# 1.net
KiCad netlist of a schematic drawn in Altium Designer
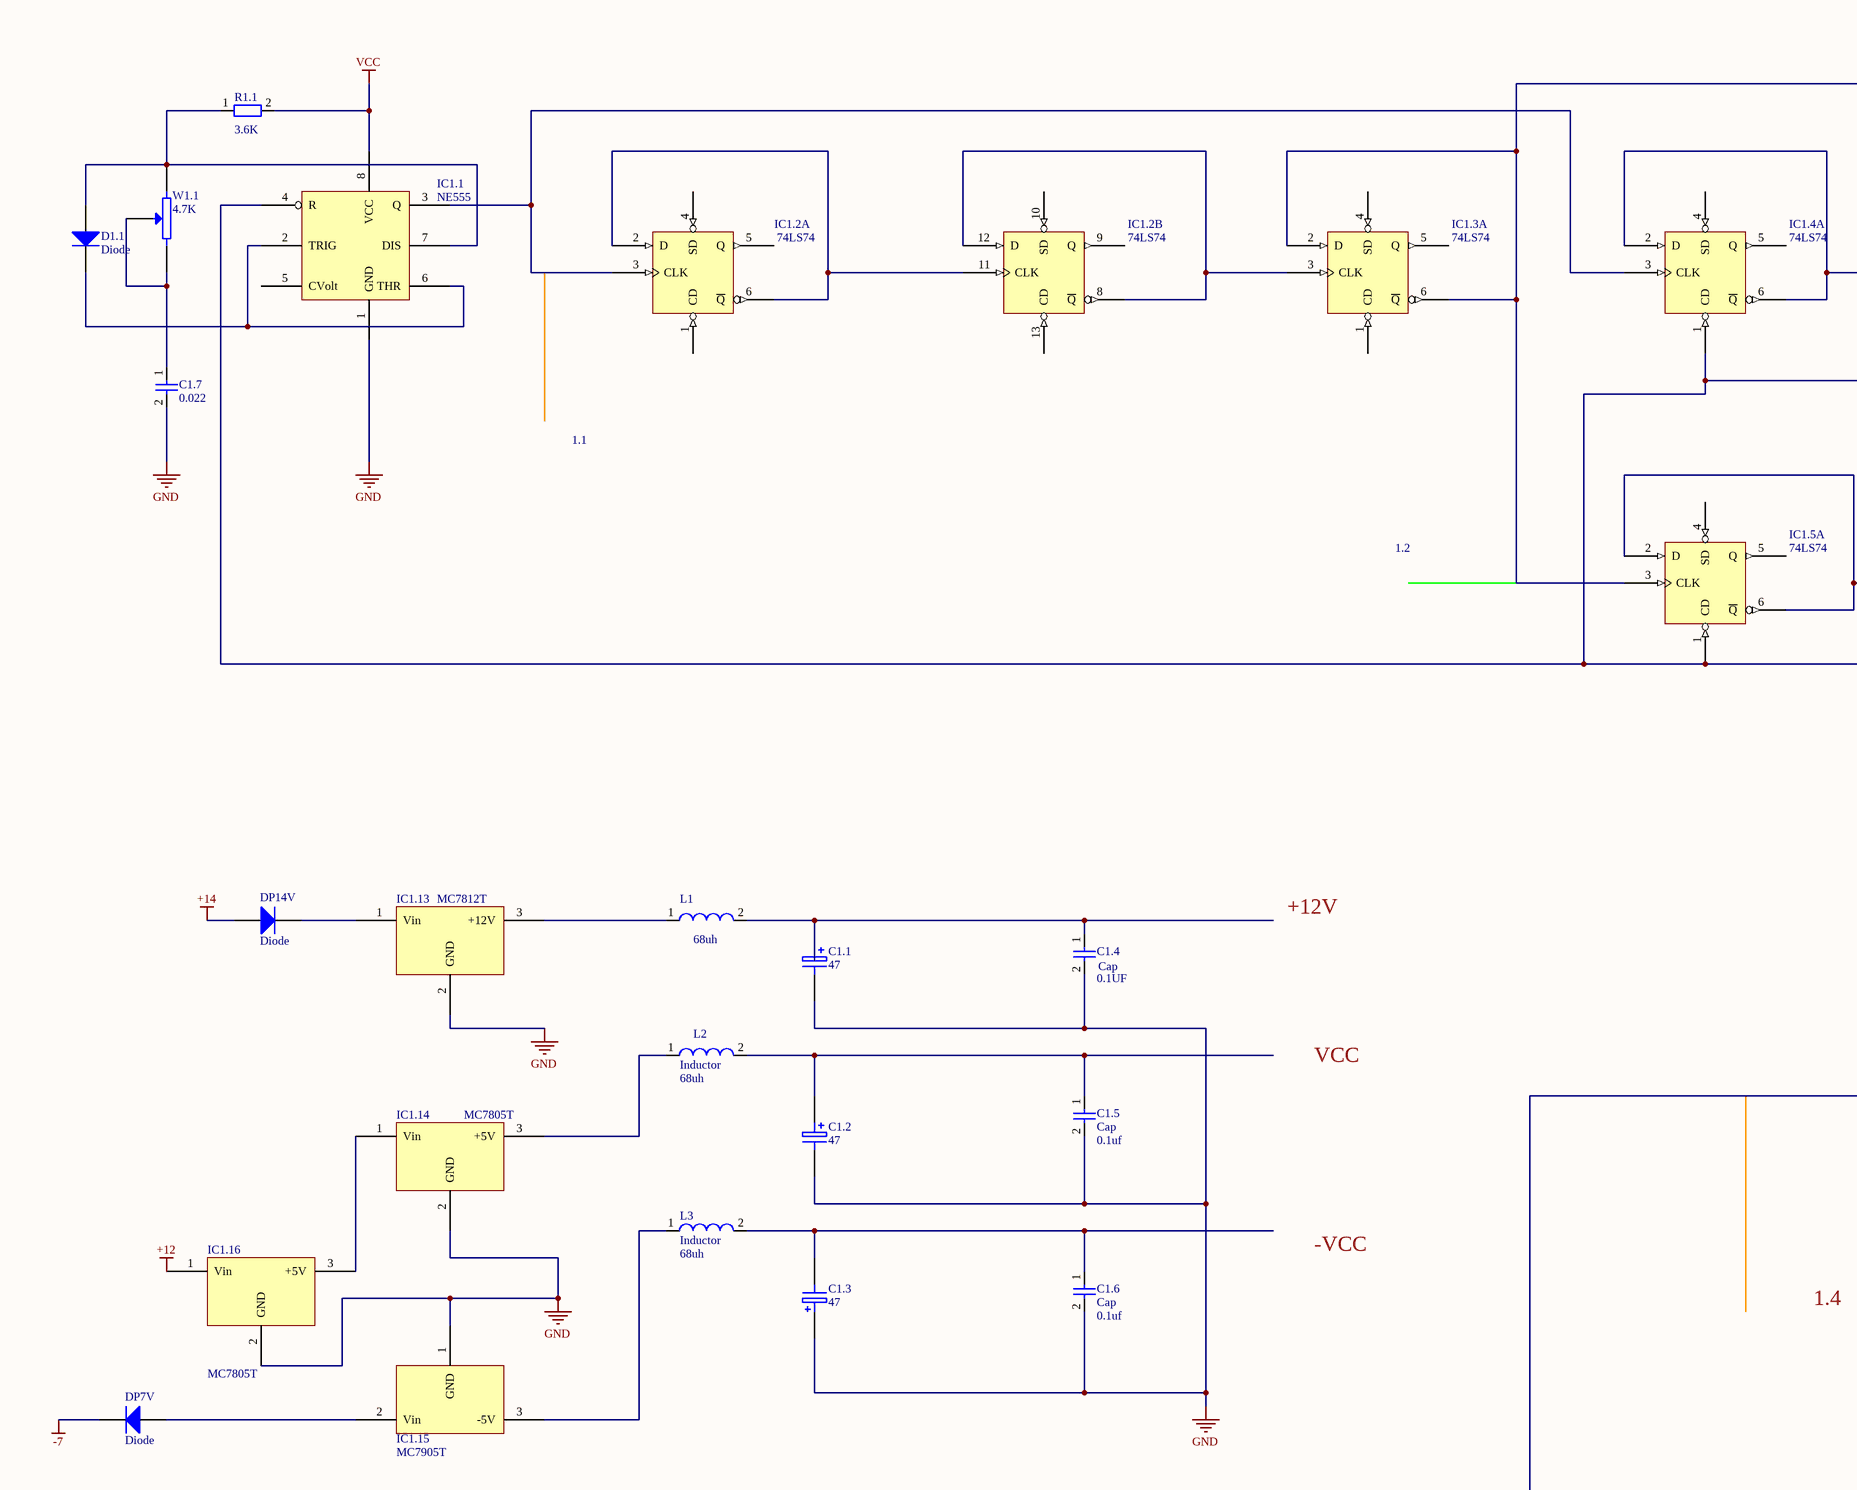
[diagram p0: 1.SchDoc, top left]
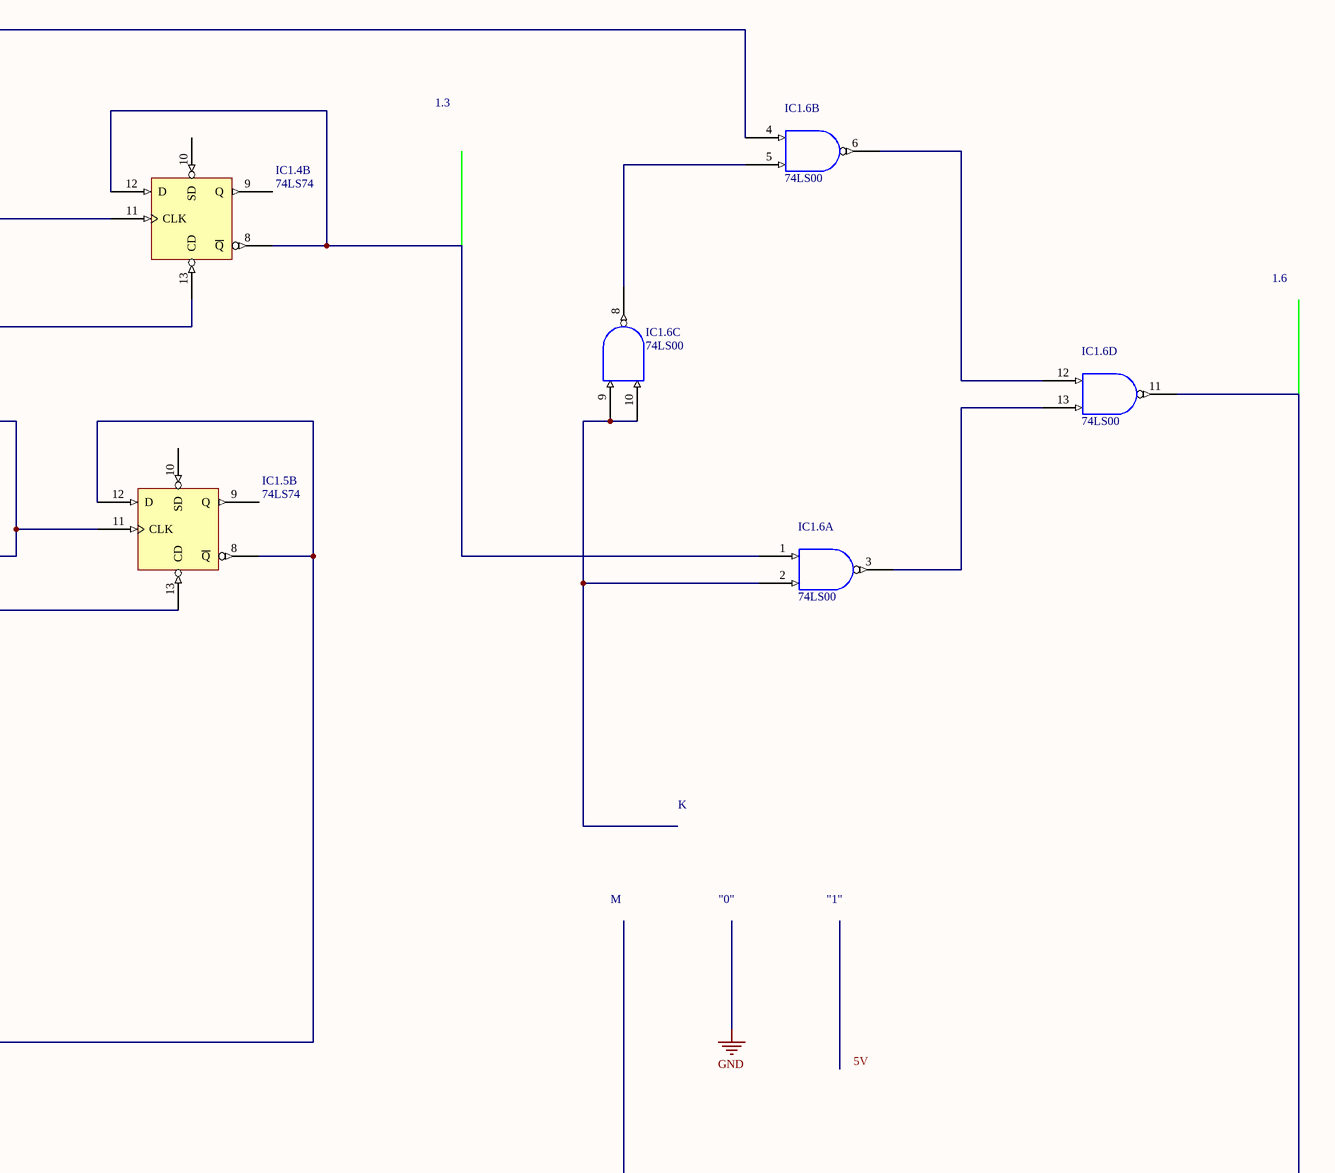
[diagram p1: 1.SchDoc, top right]
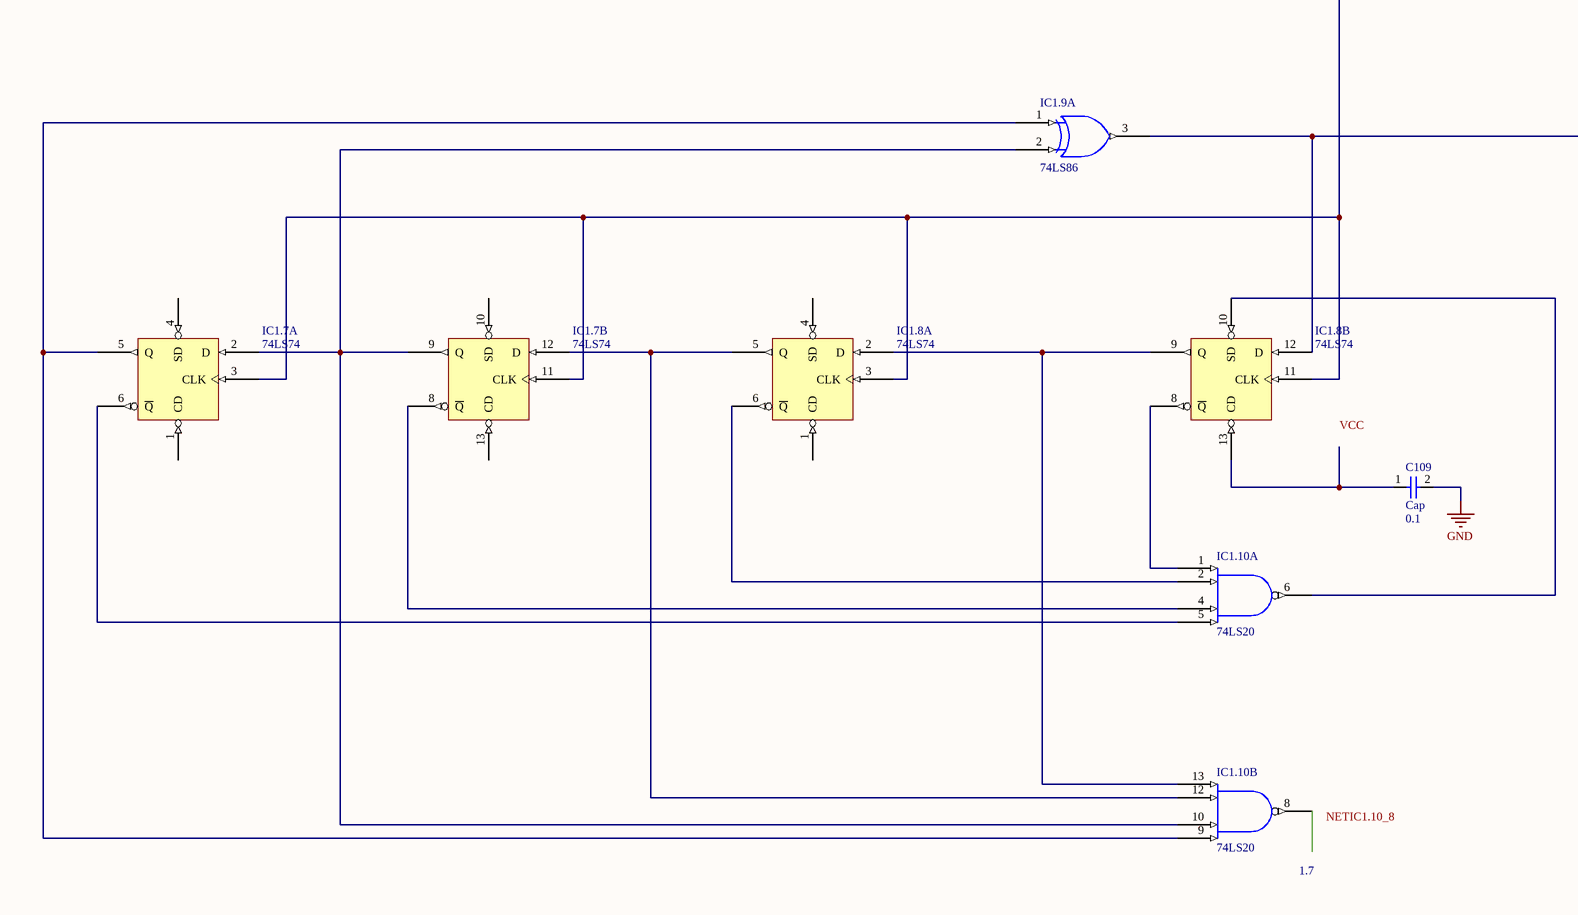
[diagram p2: 1.SchDoc, bottom left]
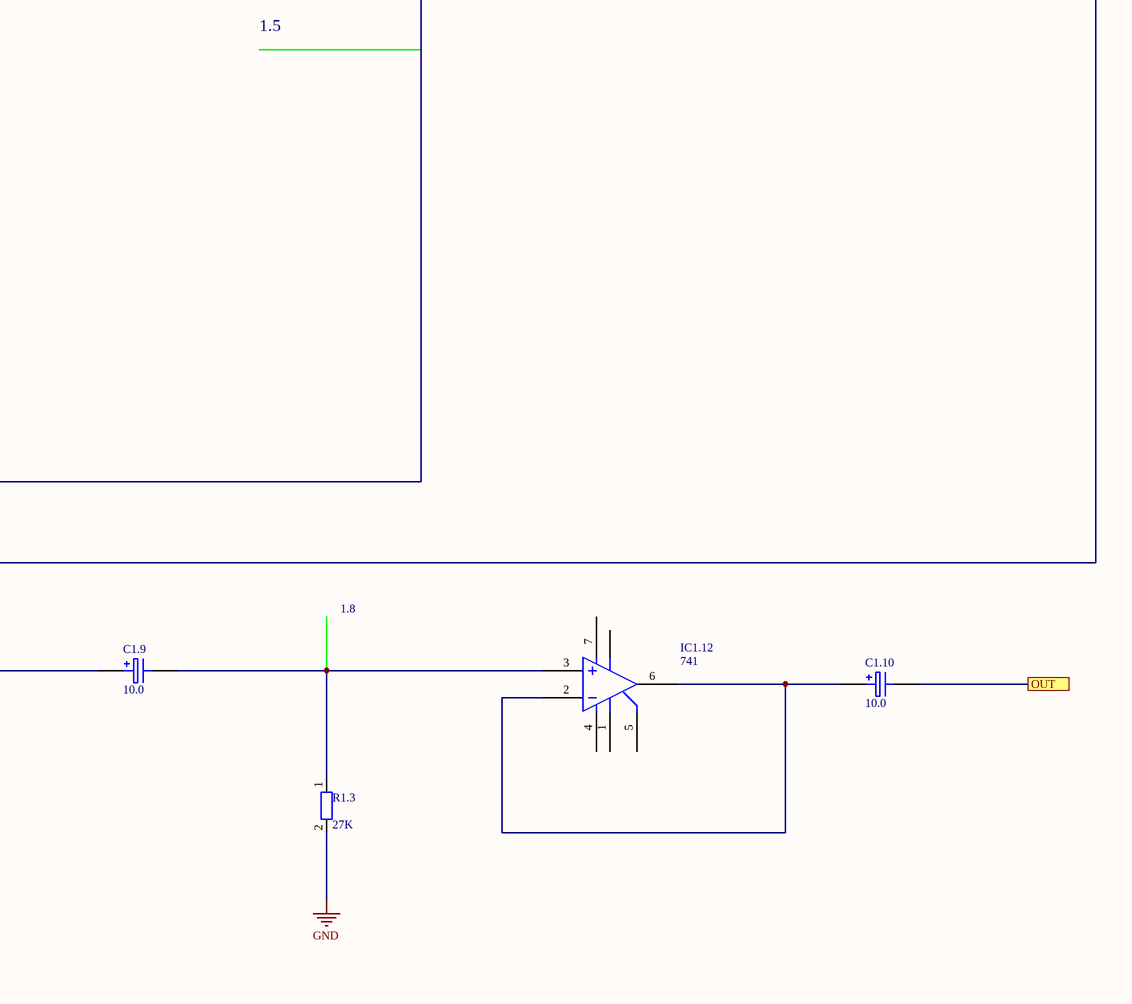
[diagram p3: 1.SchDoc, bottom right]

(export (version "E")
  (design (tool "Eeschema 10.0.6"))
  (components
    (comp (ref "C1.1")
      (value "47")
      (footprint "RAD-0.1")
      (description "Electrolytic Capacitor")
      (libsource (lib "Miscellaneous Devices1") (part "ELECTRO1"))
    )
    (comp (ref "C1.2")
      (value "47")
      (footprint "RAD-0.1")
      (description "Electrolytic Capacitor")
      (libsource (lib "Miscellaneous Devices1") (part "ELECTRO1"))
    )
    (comp (ref "C1.3")
      (value "47")
      (footprint "RAD-0.1")
      (description "Electrolytic Capacitor")
      (libsource (lib "Miscellaneous Devices1") (part "ELECTRO1"))
    )
    (comp (ref "C1.4")
      (value "Cap")
      (footprint "RAD-0.3")
      (description "Capacitor")
      (fields (field (name "ALTIUM_VALUE") "0.1UF") (field (name "PUBLISHER") "Altium Limited"))
      (libsource (lib "Miscellaneous Devices") (part "Cap"))
    )
    (comp (ref "C1.5")
      (value "Cap")
      (footprint "RAD-0.3")
      (description "Capacitor")
      (fields (field (name "ALTIUM_VALUE") "0.1uf") (field (name "PUBLISHER") "Altium Limited"))
      (libsource (lib "Miscellaneous Devices") (part "Cap"))
    )
    (comp (ref "C1.6")
      (value "Cap")
      (footprint "RAD-0.3")
      (description "Capacitor")
      (fields (field (name "ALTIUM_VALUE") "0.1uf") (field (name "PUBLISHER") "Altium Limited"))
      (libsource (lib "Miscellaneous Devices") (part "Cap"))
    )
    (comp (ref "C1.7")
      (value "0.022")
      (footprint "RAD-0.3")
      (description "Capacitor")
      (fields (field (name "Comment") "Cap") (field (name "PUBLISHER") "Altium Limited"))
      (libsource (lib "Miscellaneous Devices") (part "Cap"))
    )
    (comp (ref "C1.9")
      (value "10.0")
      (footprint "RAD-0.1")
      (description "Electrolytic Capacitor")
      (libsource (lib "Miscellaneous Devices1") (part "ELECTRO1"))
    )
    (comp (ref "C1.10")
      (value "10.0")
      (footprint "RAD-0.1")
      (description "Electrolytic Capacitor")
      (libsource (lib "Miscellaneous Devices1") (part "ELECTRO1"))
    )
    (comp (ref "C109")
      (value "Cap")
      (footprint "RAD-0.3")
      (description "Capacitor")
      (fields (field (name "ALTIUM_VALUE") "0.1") (field (name "PUBLISHER") "Altium Limited"))
      (libsource (lib "Miscellaneous Devices") (part "Cap"))
    )
    (comp (ref "D1.1")
      (value "Diode")
      (footprint "SMC")
      (description "Default Diode")
      (fields (field (name "PUBLISHER") "Altium Limited"))
      (libsource (lib "Miscellaneous Devices") (part "Diode"))
    )
    (comp (ref "DP7V")
      (value "Diode")
      (footprint "SMC")
      (description "Default Diode")
      (fields (field (name "PUBLISHER") "Altium Limited"))
      (libsource (lib "Miscellaneous Devices") (part "Diode"))
    )
    (comp (ref "DP14V")
      (value "Diode")
      (footprint "SMC")
      (description "Default Diode")
      (fields (field (name "PUBLISHER") "Altium Limited"))
      (libsource (lib "Miscellaneous Devices") (part "Diode"))
    )
    (comp (ref "IC1.1")
      (value "NE555")
      (footprint "DIP-8")
      (libsource (lib "Protel DOS Schematic Linear") (part "555"))
    )
    (comp (ref "IC1.2")
      (value "74LS74")
      (footprint "DIP-14")
      (libsource (lib "Protel DOS Schematic Voltage Regulators") (part "74LS74"))
    )
    (comp (ref "IC1.3")
      (value "74LS74")
      (footprint "DIP-14")
      (libsource (lib "Protel DOS Schematic TTL") (part "74LS74"))
    )
    (comp (ref "IC1.4")
      (value "74LS74")
      (footprint "DIP-14")
      (libsource (lib "Protel DOS Schematic TTL") (part "74LS74"))
    )
    (comp (ref "IC1.5")
      (value "74LS74")
      (footprint "DIP-14")
      (libsource (lib "Protel DOS Schematic TTL") (part "74LS74"))
    )
    (comp (ref "IC1.6")
      (value "74LS00")
      (footprint "DIP-14")
      (libsource (lib "Protel DOS Schematic TTL") (part "74LS00"))
    )
    (comp (ref "IC1.7") (value "74LS74") (footprint "DIP-14") (libsource (lib "") (part "74LS74_1")))
    (comp (ref "IC1.8") (value "74LS74") (footprint "DIP-14") (libsource (lib "") (part "74LS74_1")))
    (comp (ref "IC1.9")
      (value "74LS86")
      (footprint "DIP-14")
      (libsource (lib "Protel DOS Schematic TTL") (part "74LS86"))
    )
    (comp (ref "IC1.10")
      (value "74LS20")
      (footprint "DIP-14")
      (libsource (lib "Protel DOS Schematic TTL") (part "74LS20"))
    )
    (comp (ref "IC1.12")
      (value "741")
      (footprint "DIP-8")
      (libsource (lib "Protel DOS Schematic Operational Amplifiers") (part "741"))
    )
    (comp (ref "IC1.13")
      (value "MC7812T")
      (footprint "TO-220-AB")
      (libsource (lib "Protel DOS Schematic Voltage Regulators") (part "MC7812T"))
    )
    (comp (ref "IC1.14")
      (value "MC7805T")
      (footprint "TO-220-AB")
      (libsource (lib "Protel DOS Schematic Voltage Regulators") (part "MC7805T"))
    )
    (comp (ref "IC1.15")
      (value "MC7905T")
      (footprint "TO-220-AB")
      (libsource (lib "Protel DOS Schematic Voltage Regulators") (part "MC7905T"))
    )
    (comp (ref "IC1.16")
      (value "MC7805T")
      (footprint "TO-220-AB")
      (libsource (lib "Protel DOS Schematic Voltage Regulators") (part "MC7805T"))
    )
    (comp (ref "L1")
      (value "68uh")
      (footprint "0402-A")
      (description "Inductor")
      (fields (field (name "PUBLISHER") "Altium Limited"))
      (libsource (lib "Miscellaneous Devices") (part "Inductor"))
    )
    (comp (ref "L2")
      (value "Inductor")
      (footprint "0402-A")
      (fields (field (name "ALTIUM_VALUE") "68uh") (field (name "PUBLISHER") "Altium Limited"))
      (libsource (lib "Miscellaneous Devices") (part "Inductor"))
    )
    (comp (ref "L3")
      (value "Inductor")
      (footprint "0402-A")
      (fields (field (name "ALTIUM_VALUE") "68uh") (field (name "PUBLISHER") "Altium Limited"))
      (libsource (lib "Miscellaneous Devices") (part "Inductor"))
    )
    (comp (ref "R1.1")
      (value "3.6K")
      (footprint "AXIAL-0.4")
      (description "Resistor")
      (fields (field (name "Comment") "Res2") (field (name "PUBLISHER") "Altium Limited"))
      (libsource (lib "Miscellaneous Devices") (part "Res2"))
    )
    (comp (ref "R1.3")
      (value "27K")
      (footprint "AXIAL-0.4")
      (description "Resistor")
      (fields (field (name "PUBLISHER") "Altium Limited"))
      (libsource (lib "") (part "Res2_1"))
    )
    (comp (ref "W1.1")
      (value "4.7K")
      (footprint "VR3")
      (description "Potentiometer")
      (libsource (lib "Miscellaneous Devices1") (part "POT2"))
    )
  )
  (nets
    (net (code "1") (name "+12") (class "Default")
      (node (ref "IC1.16") (pin "1") (pinfunction "Vin_1") (pintype "passive"))
    )
    (net (code "2") (name "+14") (class "Default")
      (node (ref "DP14V") (pin "1") (pinfunction "A_1") (pintype "passive"))
    )
    (net (code "3") (name "-7") (class "Default")
      (node (ref "DP7V") (pin "2") (pinfunction "K_2") (pintype "passive"))
    )
    (net (code "4") (name "/OUT") (class "Default")
      (node (ref "C1.10") (pin "2") (pinfunction "2_2") (pintype "passive"))
    )
    (net (code "5") (name "GND") (class "Default")
      (node (ref "C1.1") (pin "2") (pinfunction "2_2") (pintype "passive"))
      (node (ref "C1.2") (pin "2") (pinfunction "2_2") (pintype "passive"))
      (node (ref "C1.3") (pin "1") (pinfunction "1_1") (pintype "passive"))
      (node (ref "C1.4") (pin "2") (pinfunction "2_2") (pintype "passive"))
      (node (ref "C1.5") (pin "2") (pinfunction "2_2") (pintype "passive"))
      (node (ref "C1.6") (pin "2") (pinfunction "2_2") (pintype "passive"))
      (node (ref "C1.7") (pin "2") (pinfunction "2_2") (pintype "passive"))
      (node (ref "C109") (pin "2") (pinfunction "2_2") (pintype "passive"))
      (node (ref "IC1.1") (pin "1") (pinfunction "GND_1") (pintype "passive"))
      (node (ref "IC1.10") (pin "7") (pinfunction "GND_7") (pintype "power_in"))
      (node (ref "IC1.13") (pin "2") (pinfunction "GND_2") (pintype "passive"))
      (node (ref "IC1.14") (pin "2") (pinfunction "GND_2") (pintype "passive"))
      (node (ref "IC1.15") (pin "1") (pinfunction "GND_1") (pintype "passive"))
      (node (ref "IC1.16") (pin "2") (pinfunction "GND_2") (pintype "passive"))
      (node (ref "IC1.2") (pin "7") (pinfunction "GND_7") (pintype "power_in"))
      (node (ref "IC1.3") (pin "7") (pinfunction "GND_7") (pintype "power_in"))
      (node (ref "IC1.4") (pin "7") (pinfunction "GND_7") (pintype "power_in"))
      (node (ref "IC1.5") (pin "7") (pinfunction "GND_7") (pintype "power_in"))
      (node (ref "IC1.6") (pin "7") (pinfunction "GND_7") (pintype "power_in"))
      (node (ref "IC1.7") (pin "7") (pinfunction "GND_7") (pintype "power_in"))
      (node (ref "IC1.8") (pin "7") (pinfunction "GND_7") (pintype "power_in"))
      (node (ref "IC1.9") (pin "7") (pinfunction "GND_7") (pintype "power_in"))
      (node (ref "R1.3") (pin "2") (pinfunction "2_2") (pintype "passive"))
    )
    (net (code "6") (name "Net-(C1.1-Pad1)") (class "Default")
      (node (ref "C1.1") (pin "1") (pinfunction "1_1") (pintype "passive"))
      (node (ref "C1.4") (pin "1") (pinfunction "1_1") (pintype "passive"))
      (node (ref "L1") (pin "2") (pinfunction "2_2") (pintype "passive"))
    )
    (net (code "7") (name "Net-(C1.2-Pad1)") (class "Default")
      (node (ref "C1.2") (pin "1") (pinfunction "1_1") (pintype "passive"))
      (node (ref "C1.5") (pin "1") (pinfunction "1_1") (pintype "passive"))
      (node (ref "L2") (pin "2") (pinfunction "2_2") (pintype "passive"))
    )
    (net (code "8") (name "Net-(C1.3-Pad2)") (class "Default")
      (node (ref "C1.3") (pin "2") (pinfunction "2_2") (pintype "passive"))
      (node (ref "C1.6") (pin "1") (pinfunction "1_1") (pintype "passive"))
      (node (ref "L3") (pin "2") (pinfunction "2_2") (pintype "passive"))
    )
    (net (code "9") (name "Net-(C1.9-Pad1)") (class "Default")
      (node (ref "C1.9") (pin "1") (pinfunction "1_1") (pintype "passive"))
      (node (ref "IC1.6") (pin "11") (pintype "output"))
    )
    (net (code "10") (name "Net-(C1.9-Pad2)") (class "Default")
      (node (ref "C1.9") (pin "2") (pinfunction "2_2") (pintype "passive"))
      (node (ref "IC1.12") (pin "3") (pintype "passive"))
      (node (ref "R1.3") (pin "1") (pinfunction "1_1") (pintype "passive"))
    )
    (net (code "11") (name "Net-(C1.10-Pad1)") (class "Default")
      (node (ref "C1.10") (pin "1") (pinfunction "1_1") (pintype "passive"))
      (node (ref "IC1.12") (pin "2") (pintype "passive"))
      (node (ref "IC1.12") (pin "6") (pintype "passive"))
    )
    (net (code "12") (name "Net-(D1.1-A)") (class "Default")
      (node (ref "D1.1") (pin "1") (pinfunction "A_1") (pintype "passive"))
      (node (ref "IC1.1") (pin "7") (pinfunction "DIS_7") (pintype "passive"))
      (node (ref "R1.1") (pin "1") (pinfunction "1_1") (pintype "passive"))
      (node (ref "W1.1") (pin "2") (pinfunction "2_2") (pintype "passive"))
    )
    (net (code "13") (name "Net-(D1.1-K)") (class "Default")
      (node (ref "D1.1") (pin "2") (pinfunction "K_2") (pintype "passive"))
      (node (ref "IC1.1") (pin "2") (pinfunction "TRIG_2") (pintype "passive"))
      (node (ref "IC1.1") (pin "6") (pinfunction "THR_6") (pintype "passive"))
    )
    (net (code "14") (name "Net-(DP7V-A)") (class "Default")
      (node (ref "DP7V") (pin "1") (pinfunction "A_1") (pintype "passive"))
      (node (ref "IC1.15") (pin "2") (pinfunction "Vin_2") (pintype "passive"))
    )
    (net (code "15") (name "Net-(DP14V-K)") (class "Default")
      (node (ref "DP14V") (pin "2") (pinfunction "K_2") (pintype "passive"))
      (node (ref "IC1.13") (pin "1") (pinfunction "Vin_1") (pintype "passive"))
    )
    (net (code "16") (name "Net-(IC1.1-Q)") (class "Default")
      (node (ref "IC1.1") (pin "3") (pinfunction "Q_3") (pintype "passive"))
      (node (ref "IC1.2") (pin "3") (pinfunction "CLK_3") (pintype "input"))
      (node (ref "IC1.4") (pin "3") (pinfunction "CLK_3") (pintype "input"))
    )
    (net (code "17") (name "Net-(IC1.1-R)") (class "Default")
      (node (ref "IC1.1") (pin "4") (pinfunction "R_4") (pintype "passive"))
      (node (ref "IC1.4") (pin "1") (pinfunction "CD_1") (pintype "input"))
      (node (ref "IC1.4") (pin "13") (pinfunction "CD_13") (pintype "input"))
      (node (ref "IC1.5") (pin "1") (pinfunction "CD_1") (pintype "input"))
      (node (ref "IC1.5") (pin "13") (pinfunction "CD_13") (pintype "input"))
    )
    (net (code "18") (name "Net-(IC1.2A-D)") (class "Default")
      (node (ref "IC1.2") (pin "11") (pinfunction "CLK_11") (pintype "input"))
      (node (ref "IC1.2") (pin "2") (pinfunction "D_2") (pintype "input"))
      (node (ref "IC1.2") (pin "6") (pinfunction "~{Q}_6") (pintype "output"))
    )
    (net (code "19") (name "Net-(IC1.2B-D)") (class "Default")
      (node (ref "IC1.2") (pin "12") (pinfunction "D_12") (pintype "input"))
      (node (ref "IC1.2") (pin "8") (pinfunction "~{Q}_8") (pintype "output"))
      (node (ref "IC1.3") (pin "3") (pinfunction "CLK_3") (pintype "input"))
    )
    (net (code "20") (name "Net-(IC1.3A-D)") (class "Default")
      (node (ref "IC1.3") (pin "2") (pinfunction "D_2") (pintype "input"))
      (node (ref "IC1.3") (pin "6") (pinfunction "~{Q}_6") (pintype "output"))
      (node (ref "IC1.5") (pin "3") (pinfunction "CLK_3") (pintype "input"))
      (node (ref "IC1.6") (pin "4") (pintype "input"))
    )
    (net (code "21") (name "Net-(IC1.4A-D)") (class "Default")
      (node (ref "IC1.4") (pin "11") (pinfunction "CLK_11") (pintype "input"))
      (node (ref "IC1.4") (pin "2") (pinfunction "D_2") (pintype "input"))
      (node (ref "IC1.4") (pin "6") (pinfunction "~{Q}_6") (pintype "output"))
    )
    (net (code "22") (name "Net-(IC1.4B-D)") (class "Default")
      (node (ref "IC1.4") (pin "12") (pinfunction "D_12") (pintype "input"))
      (node (ref "IC1.4") (pin "8") (pinfunction "~{Q}_8") (pintype "output"))
      (node (ref "IC1.6") (pin "1") (pintype "input"))
    )
    (net (code "23") (name "Net-(IC1.5A-D)") (class "Default")
      (node (ref "IC1.5") (pin "11") (pinfunction "CLK_11") (pintype "input"))
      (node (ref "IC1.5") (pin "2") (pinfunction "D_2") (pintype "input"))
      (node (ref "IC1.5") (pin "6") (pinfunction "~{Q}_6") (pintype "output"))
    )
    (net (code "24") (name "Net-(IC1.5B-D)") (class "Default")
      (node (ref "IC1.5") (pin "12") (pinfunction "D_12") (pintype "input"))
      (node (ref "IC1.5") (pin "8") (pinfunction "~{Q}_8") (pintype "output"))
      (node (ref "IC1.7") (pin "11") (pinfunction "CLK_11") (pintype "input"))
      (node (ref "IC1.7") (pin "3") (pinfunction "CLK_3") (pintype "input"))
      (node (ref "IC1.8") (pin "11") (pinfunction "CLK_11") (pintype "input"))
      (node (ref "IC1.8") (pin "3") (pinfunction "CLK_3") (pintype "input"))
    )
    (net (code "25") (name "Net-(IC1.6-Pad5)") (class "Default")
      (node (ref "IC1.6") (pin "5") (pintype "input"))
      (node (ref "IC1.6") (pin "8") (pintype "output"))
    )
    (net (code "26") (name "Net-(IC1.6-Pad10)") (class "Default")
      (node (ref "IC1.6") (pin "10") (pintype "input"))
      (node (ref "IC1.6") (pin "2") (pintype "input"))
      (node (ref "IC1.6") (pin "9") (pintype "input"))
    )
    (net (code "27") (name "Net-(IC1.6-Pad12)") (class "Default")
      (node (ref "IC1.6") (pin "12") (pintype "input"))
      (node (ref "IC1.6") (pin "6") (pintype "output"))
    )
    (net (code "28") (name "Net-(IC1.6-Pad13)") (class "Default")
      (node (ref "IC1.6") (pin "13") (pintype "input"))
      (node (ref "IC1.6") (pin "3") (pintype "output"))
    )
    (net (code "29") (name "Net-(IC1.7A-D)") (class "Default")
      (node (ref "IC1.10") (pin "10") (pintype "input"))
      (node (ref "IC1.7") (pin "2") (pinfunction "D_2") (pintype "input"))
      (node (ref "IC1.7") (pin "9") (pinfunction "Q_9") (pintype "output"))
      (node (ref "IC1.9") (pin "2") (pintype "input"))
    )
    (net (code "30") (name "Net-(IC1.7A-Q)") (class "Default")
      (node (ref "IC1.10") (pin "9") (pintype "input"))
      (node (ref "IC1.7") (pin "5") (pinfunction "Q_5") (pintype "output"))
      (node (ref "IC1.9") (pin "1") (pintype "input"))
    )
    (net (code "31") (name "Net-(IC1.7A-~{Q})") (class "Default")
      (node (ref "IC1.10") (pin "5") (pintype "input"))
      (node (ref "IC1.7") (pin "6") (pinfunction "~{Q}_6") (pintype "output"))
    )
    (net (code "32") (name "Net-(IC1.7B-D)") (class "Default")
      (node (ref "IC1.10") (pin "12") (pintype "input"))
      (node (ref "IC1.7") (pin "12") (pinfunction "D_12") (pintype "input"))
      (node (ref "IC1.8") (pin "5") (pinfunction "Q_5") (pintype "output"))
    )
    (net (code "33") (name "Net-(IC1.7B-~{Q})") (class "Default")
      (node (ref "IC1.10") (pin "4") (pintype "input"))
      (node (ref "IC1.7") (pin "8") (pinfunction "~{Q}_8") (pintype "output"))
    )
    (net (code "34") (name "Net-(IC1.8A-D)") (class "Default")
      (node (ref "IC1.10") (pin "13") (pintype "input"))
      (node (ref "IC1.8") (pin "2") (pinfunction "D_2") (pintype "input"))
      (node (ref "IC1.8") (pin "9") (pinfunction "Q_9") (pintype "output"))
    )
    (net (code "35") (name "Net-(IC1.8A-~{Q})") (class "Default")
      (node (ref "IC1.10") (pin "2") (pintype "input"))
      (node (ref "IC1.8") (pin "6") (pinfunction "~{Q}_6") (pintype "output"))
    )
    (net (code "36") (name "Net-(IC1.8B-CD)") (class "Default")
      (node (ref "C109") (pin "1") (pinfunction "1_1") (pintype "passive"))
      (node (ref "IC1.8") (pin "13") (pinfunction "CD_13") (pintype "input"))
    )
    (net (code "37") (name "Net-(IC1.8B-D)") (class "Default")
      (node (ref "IC1.8") (pin "12") (pinfunction "D_12") (pintype "input"))
      (node (ref "IC1.9") (pin "3") (pintype "output"))
    )
    (net (code "38") (name "Net-(IC1.8B-SD)") (class "Default")
      (node (ref "IC1.10") (pin "6") (pintype "output"))
      (node (ref "IC1.8") (pin "10") (pinfunction "SD_10") (pintype "input"))
    )
    (net (code "39") (name "Net-(IC1.8B-~{Q})") (class "Default")
      (node (ref "IC1.10") (pin "1") (pintype "input"))
      (node (ref "IC1.8") (pin "8") (pinfunction "~{Q}_8") (pintype "output"))
    )
    (net (code "40") (name "Net-(IC1.13-+12V)") (class "Default")
      (node (ref "IC1.13") (pin "3") (pinfunction "+12V_3") (pintype "passive"))
      (node (ref "L1") (pin "1") (pinfunction "1_1") (pintype "passive"))
    )
    (net (code "41") (name "Net-(IC1.14-+5V)") (class "Default")
      (node (ref "IC1.14") (pin "3") (pinfunction "+5V_3") (pintype "passive"))
      (node (ref "L2") (pin "1") (pinfunction "1_1") (pintype "passive"))
    )
    (net (code "42") (name "Net-(IC1.14-Vin)") (class "Default")
      (node (ref "IC1.14") (pin "1") (pinfunction "Vin_1") (pintype "passive"))
      (node (ref "IC1.16") (pin "3") (pinfunction "+5V_3") (pintype "passive"))
    )
    (net (code "43") (name "Net-(IC1.15--5V)") (class "Default")
      (node (ref "IC1.15") (pin "3") (pinfunction "-5V_3") (pintype "passive"))
      (node (ref "L3") (pin "1") (pinfunction "1_1") (pintype "passive"))
    )
    (net (code "44") (name "Net-(W1.1-W)") (class "Default")
      (node (ref "C1.7") (pin "1") (pinfunction "1_1") (pintype "passive"))
      (node (ref "W1.1") (pin "1") (pinfunction "1_1") (pintype "passive"))
      (node (ref "W1.1") (pin "3") (pinfunction "W_3") (pintype "passive"))
    )
    (net (code "45") (name "VCC") (class "Default")
      (node (ref "IC1.1") (pin "8") (pinfunction "VCC_8") (pintype "passive"))
      (node (ref "IC1.10") (pin "14") (pinfunction "VCC_14") (pintype "power_in"))
      (node (ref "IC1.2") (pin "14") (pinfunction "VCC_14") (pintype "power_in"))
      (node (ref "IC1.3") (pin "14") (pinfunction "VCC_14") (pintype "power_in"))
      (node (ref "IC1.4") (pin "14") (pinfunction "VCC_14") (pintype "power_in"))
      (node (ref "IC1.5") (pin "14") (pinfunction "VCC_14") (pintype "power_in"))
      (node (ref "IC1.6") (pin "14") (pinfunction "VCC_14") (pintype "power_in"))
      (node (ref "IC1.7") (pin "14") (pinfunction "VCC_14") (pintype "power_in"))
      (node (ref "IC1.8") (pin "14") (pinfunction "VCC_14") (pintype "power_in"))
      (node (ref "IC1.9") (pin "14") (pinfunction "VCC_14") (pintype "power_in"))
      (node (ref "R1.1") (pin "2") (pinfunction "2_2") (pintype "passive"))
    )
    (net (code "46") (name "unconnected-(IC1.1-CVolt-Pad5)") (class "Default")
      (node (ref "IC1.1") (pin "5") (pinfunction "CVolt_5") (pintype "passive"))
    )
    (net (code "47") (name "unconnected-(IC1.2A-CD-Pad1)") (class "Default")
      (node (ref "IC1.2") (pin "1") (pinfunction "CD_1") (pintype "input"))
    )
    (net (code "48") (name "unconnected-(IC1.2A-Q-Pad5)") (class "Default")
      (node (ref "IC1.2") (pin "5") (pinfunction "Q_5") (pintype "output"))
    )
    (net (code "49") (name "unconnected-(IC1.2A-SD-Pad4)") (class "Default")
      (node (ref "IC1.2") (pin "4") (pinfunction "SD_4") (pintype "input"))
    )
    (net (code "50") (name "unconnected-(IC1.2B-CD-Pad13)") (class "Default")
      (node (ref "IC1.2") (pin "13") (pinfunction "CD_13") (pintype "input"))
    )
    (net (code "51") (name "unconnected-(IC1.2B-Q-Pad9)") (class "Default")
      (node (ref "IC1.2") (pin "9") (pinfunction "Q_9") (pintype "output"))
    )
    (net (code "52") (name "unconnected-(IC1.2B-SD-Pad10)") (class "Default")
      (node (ref "IC1.2") (pin "10") (pinfunction "SD_10") (pintype "input"))
    )
    (net (code "53") (name "unconnected-(IC1.3A-CD-Pad1)") (class "Default")
      (node (ref "IC1.3") (pin "1") (pinfunction "CD_1") (pintype "input"))
    )
    (net (code "54") (name "unconnected-(IC1.3A-Q-Pad5)") (class "Default")
      (node (ref "IC1.3") (pin "5") (pinfunction "Q_5") (pintype "output"))
    )
    (net (code "55") (name "unconnected-(IC1.3A-SD-Pad4)") (class "Default")
      (node (ref "IC1.3") (pin "4") (pinfunction "SD_4") (pintype "input"))
    )
    (net (code "56") (name "unconnected-(IC1.4A-Q-Pad5)") (class "Default")
      (node (ref "IC1.4") (pin "5") (pinfunction "Q_5") (pintype "output"))
    )
    (net (code "57") (name "unconnected-(IC1.4A-SD-Pad4)") (class "Default")
      (node (ref "IC1.4") (pin "4") (pinfunction "SD_4") (pintype "input"))
    )
    (net (code "58") (name "unconnected-(IC1.4B-Q-Pad9)") (class "Default")
      (node (ref "IC1.4") (pin "9") (pinfunction "Q_9") (pintype "output"))
    )
    (net (code "59") (name "unconnected-(IC1.4B-SD-Pad10)") (class "Default")
      (node (ref "IC1.4") (pin "10") (pinfunction "SD_10") (pintype "input"))
    )
    (net (code "60") (name "unconnected-(IC1.5A-Q-Pad5)") (class "Default")
      (node (ref "IC1.5") (pin "5") (pinfunction "Q_5") (pintype "output"))
    )
    (net (code "61") (name "unconnected-(IC1.5A-SD-Pad4)") (class "Default")
      (node (ref "IC1.5") (pin "4") (pinfunction "SD_4") (pintype "input"))
    )
    (net (code "62") (name "unconnected-(IC1.5B-Q-Pad9)") (class "Default")
      (node (ref "IC1.5") (pin "9") (pinfunction "Q_9") (pintype "output"))
    )
    (net (code "63") (name "unconnected-(IC1.5B-SD-Pad10)") (class "Default")
      (node (ref "IC1.5") (pin "10") (pinfunction "SD_10") (pintype "input"))
    )
    (net (code "64") (name "unconnected-(IC1.7A-CD-Pad1)") (class "Default")
      (node (ref "IC1.7") (pin "1") (pinfunction "CD_1") (pintype "input"))
    )
    (net (code "65") (name "unconnected-(IC1.7A-SD-Pad4)") (class "Default")
      (node (ref "IC1.7") (pin "4") (pinfunction "SD_4") (pintype "input"))
    )
    (net (code "66") (name "unconnected-(IC1.7B-CD-Pad13)") (class "Default")
      (node (ref "IC1.7") (pin "13") (pinfunction "CD_13") (pintype "input"))
    )
    (net (code "67") (name "unconnected-(IC1.7B-SD-Pad10)") (class "Default")
      (node (ref "IC1.7") (pin "10") (pinfunction "SD_10") (pintype "input"))
    )
    (net (code "68") (name "unconnected-(IC1.8A-CD-Pad1)") (class "Default")
      (node (ref "IC1.8") (pin "1") (pinfunction "CD_1") (pintype "input"))
    )
    (net (code "69") (name "unconnected-(IC1.8A-SD-Pad4)") (class "Default")
      (node (ref "IC1.8") (pin "4") (pinfunction "SD_4") (pintype "input"))
    )
    (net (code "70") (name "unconnected-(IC1.10-Pad8)") (class "Default")
      (node (ref "IC1.10") (pin "8") (pintype "output"))
    )
    (net (code "71") (name "unconnected-(IC1.12-Pad1)") (class "Default")
      (node (ref "IC1.12") (pin "1") (pintype "passive"))
    )
    (net (code "72") (name "unconnected-(IC1.12-Pad4)") (class "Default")
      (node (ref "IC1.12") (pin "4") (pintype "passive"))
    )
    (net (code "73") (name "unconnected-(IC1.12-Pad5)") (class "Default")
      (node (ref "IC1.12") (pin "5") (pintype "passive"))
    )
    (net (code "74") (name "unconnected-(IC1.12-Pad7)") (class "Default")
      (node (ref "IC1.12") (pin "7") (pintype "passive"))
    )
  )
)
